# covox.net
KiCad netlist of a schematic drawn in EAGLE
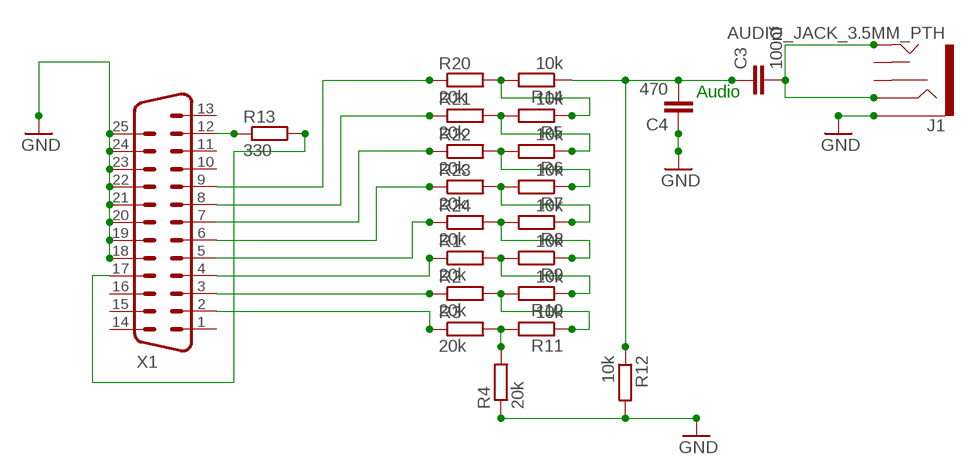
[diagram p0: schematic, sheet 1]

(export (version "E")
  (design (tool "Eeschema 10.0.6"))
  (components
    (comp (ref "C3")
      (value "100nf")
      (footprint "eagle-import:C0805K")
      (libsource (lib "eagle-import") (part "C-EUC0805K"))
    )
    (comp (ref "C4")
      (value "470")
      (footprint "eagle-import:C0805K")
      (libsource (lib "eagle-import") (part "C-EUC0805K"))
    )
    (comp (ref "J1")
      (value "AUDIO_JACK_3.5MM_PTH")
      (footprint "eagle-import:AUDIO-JACK")
      (libsource (lib "eagle-import") (part "AUDIO_JACK_3.5MM_PTH"))
    )
    (comp (ref "R1")
      (value "20k")
      (footprint "eagle-import:M0805")
      (libsource (lib "eagle-import") (part "R-EU_M0805"))
    )
    (comp (ref "R2")
      (value "20k")
      (footprint "eagle-import:M0805")
      (libsource (lib "eagle-import") (part "R-EU_M0805"))
    )
    (comp (ref "R3")
      (value "20k")
      (footprint "eagle-import:M0805")
      (libsource (lib "eagle-import") (part "R-EU_M0805"))
    )
    (comp (ref "R4")
      (value "20k")
      (footprint "eagle-import:M0805")
      (libsource (lib "eagle-import") (part "R-EU_M0805"))
    )
    (comp (ref "R5")
      (value "10k")
      (footprint "eagle-import:M0805")
      (libsource (lib "eagle-import") (part "R-EU_M0805"))
    )
    (comp (ref "R6")
      (value "10k")
      (footprint "eagle-import:M0805")
      (libsource (lib "eagle-import") (part "R-EU_M0805"))
    )
    (comp (ref "R7")
      (value "10k")
      (footprint "eagle-import:M0805")
      (libsource (lib "eagle-import") (part "R-EU_M0805"))
    )
    (comp (ref "R8")
      (value "10k")
      (footprint "eagle-import:M0805")
      (libsource (lib "eagle-import") (part "R-EU_M0805"))
    )
    (comp (ref "R9")
      (value "10k")
      (footprint "eagle-import:M0805")
      (libsource (lib "eagle-import") (part "R-EU_M0805"))
    )
    (comp (ref "R10")
      (value "10k")
      (footprint "eagle-import:M0805")
      (libsource (lib "eagle-import") (part "R-EU_M0805"))
    )
    (comp (ref "R11")
      (value "10k")
      (footprint "eagle-import:M0805")
      (libsource (lib "eagle-import") (part "R-EU_M0805"))
    )
    (comp (ref "R12")
      (value "10k")
      (footprint "eagle-import:M0805")
      (libsource (lib "eagle-import") (part "R-EU_M0805"))
    )
    (comp (ref "R13")
      (value "330")
      (footprint "eagle-import:M0805")
      (libsource (lib "eagle-import") (part "R-EU_M0805"))
    )
    (comp (ref "R14")
      (value "10k")
      (footprint "eagle-import:M0805")
      (libsource (lib "eagle-import") (part "R-EU_M0805"))
    )
    (comp (ref "R20")
      (value "20k")
      (footprint "eagle-import:M0805")
      (libsource (lib "eagle-import") (part "R-EU_M0805"))
    )
    (comp (ref "R21")
      (value "20k")
      (footprint "eagle-import:M0805")
      (libsource (lib "eagle-import") (part "R-EU_M0805"))
    )
    (comp (ref "R22")
      (value "20k")
      (footprint "eagle-import:M0805")
      (libsource (lib "eagle-import") (part "R-EU_M0805"))
    )
    (comp (ref "R23")
      (value "20k")
      (footprint "eagle-import:M0805")
      (libsource (lib "eagle-import") (part "R-EU_M0805"))
    )
    (comp (ref "R24")
      (value "20k")
      (footprint "eagle-import:M0805")
      (libsource (lib "eagle-import") (part "R-EU_M0805"))
    )
    (comp (ref "X1")
      (value "M25HP")
      (footprint "eagle-import:M25HP")
      (libsource (lib "eagle-import") (part "M25HP"))
    )
  )
  (nets
    (net (code "1") (name "GND") (class "Default")
      (node (ref "C4") (pin "1") (pinfunction "1_1") (pintype "passive"))
      (node (ref "J1") (pin "SLEEVE") (pinfunction "SLEEVE_SLEEVE") (pintype "bidirectional"))
      (node (ref "R12") (pin "2") (pinfunction "2_2") (pintype "passive"))
      (node (ref "R4") (pin "1") (pinfunction "1_1") (pintype "passive"))
      (node (ref "X1") (pin "18") (pinfunction "18_18") (pintype "passive"))
      (node (ref "X1") (pin "19") (pinfunction "19_19") (pintype "passive"))
      (node (ref "X1") (pin "20") (pinfunction "20_20") (pintype "passive"))
      (node (ref "X1") (pin "21") (pinfunction "21_21") (pintype "passive"))
      (node (ref "X1") (pin "22") (pinfunction "22_22") (pintype "passive"))
      (node (ref "X1") (pin "23") (pinfunction "23_23") (pintype "passive"))
      (node (ref "X1") (pin "24") (pinfunction "24_24") (pintype "passive"))
      (node (ref "X1") (pin "25") (pinfunction "25_25") (pintype "passive"))
    )
    (net (code "2") (name "Net-(C3-Pad1)") (class "Default")
      (node (ref "C3") (pin "1") (pinfunction "1_1") (pintype "passive"))
      (node (ref "C4") (pin "2") (pinfunction "2_2") (pintype "passive"))
      (node (ref "R12") (pin "1") (pinfunction "1_1") (pintype "passive"))
      (node (ref "R14") (pin "1") (pinfunction "1_1") (pintype "passive"))
    )
    (net (code "3") (name "Net-(C3-Pad2)") (class "Default")
      (node (ref "C3") (pin "2") (pinfunction "2_2") (pintype "passive"))
      (node (ref "J1") (pin "RING") (pinfunction "RING_RING") (pintype "bidirectional"))
      (node (ref "J1") (pin "TIP") (pinfunction "TIP_TIP") (pintype "bidirectional"))
    )
    (net (code "4") (name "Net-(R1-Pad1)") (class "Default")
      (node (ref "R1") (pin "1") (pinfunction "1_1") (pintype "passive"))
      (node (ref "X1") (pin "4") (pinfunction "4_4") (pintype "passive"))
    )
    (net (code "5") (name "Net-(R1-Pad2)") (class "Default")
      (node (ref "R1") (pin "2") (pinfunction "2_2") (pintype "passive"))
      (node (ref "R10") (pin "1") (pinfunction "1_1") (pintype "passive"))
      (node (ref "R9") (pin "2") (pinfunction "2_2") (pintype "passive"))
    )
    (net (code "6") (name "Net-(R2-Pad1)") (class "Default")
      (node (ref "R2") (pin "1") (pinfunction "1_1") (pintype "passive"))
      (node (ref "X1") (pin "3") (pinfunction "3_3") (pintype "passive"))
    )
    (net (code "7") (name "Net-(R3-Pad1)") (class "Default")
      (node (ref "R3") (pin "1") (pinfunction "1_1") (pintype "passive"))
      (node (ref "X1") (pin "2") (pinfunction "2_2") (pintype "passive"))
    )
    (net (code "8") (name "Net-(R10-Pad2)") (class "Default")
      (node (ref "R10") (pin "2") (pinfunction "2_2") (pintype "passive"))
      (node (ref "R11") (pin "1") (pinfunction "1_1") (pintype "passive"))
      (node (ref "R2") (pin "2") (pinfunction "2_2") (pintype "passive"))
    )
    (net (code "9") (name "Net-(R11-Pad2)") (class "Default")
      (node (ref "R11") (pin "2") (pinfunction "2_2") (pintype "passive"))
      (node (ref "R3") (pin "2") (pinfunction "2_2") (pintype "passive"))
      (node (ref "R4") (pin "2") (pinfunction "2_2") (pintype "passive"))
    )
    (net (code "10") (name "Net-(R13-Pad1)") (class "Default")
      (node (ref "R13") (pin "1") (pinfunction "1_1") (pintype "passive"))
      (node (ref "X1") (pin "12") (pinfunction "12_12") (pintype "passive"))
    )
    (net (code "11") (name "Net-(R13-Pad2)") (class "Default")
      (node (ref "R13") (pin "2") (pinfunction "2_2") (pintype "passive"))
      (node (ref "X1") (pin "17") (pinfunction "17_17") (pintype "passive"))
    )
    (net (code "12") (name "Net-(R14-Pad2)") (class "Default")
      (node (ref "R14") (pin "2") (pinfunction "2_2") (pintype "passive"))
      (node (ref "R20") (pin "2") (pinfunction "2_2") (pintype "passive"))
      (node (ref "R5") (pin "1") (pinfunction "1_1") (pintype "passive"))
    )
    (net (code "13") (name "Net-(R20-Pad1)") (class "Default")
      (node (ref "R20") (pin "1") (pinfunction "1_1") (pintype "passive"))
      (node (ref "X1") (pin "9") (pinfunction "9_9") (pintype "passive"))
    )
    (net (code "14") (name "Net-(R21-Pad1)") (class "Default")
      (node (ref "R21") (pin "1") (pinfunction "1_1") (pintype "passive"))
      (node (ref "X1") (pin "8") (pinfunction "8_8") (pintype "passive"))
    )
    (net (code "15") (name "Net-(R21-Pad2)") (class "Default")
      (node (ref "R21") (pin "2") (pinfunction "2_2") (pintype "passive"))
      (node (ref "R5") (pin "2") (pinfunction "2_2") (pintype "passive"))
      (node (ref "R6") (pin "1") (pinfunction "1_1") (pintype "passive"))
    )
    (net (code "16") (name "Net-(R22-Pad1)") (class "Default")
      (node (ref "R22") (pin "1") (pinfunction "1_1") (pintype "passive"))
      (node (ref "X1") (pin "7") (pinfunction "7_7") (pintype "passive"))
    )
    (net (code "17") (name "Net-(R22-Pad2)") (class "Default")
      (node (ref "R22") (pin "2") (pinfunction "2_2") (pintype "passive"))
      (node (ref "R6") (pin "2") (pinfunction "2_2") (pintype "passive"))
      (node (ref "R7") (pin "1") (pinfunction "1_1") (pintype "passive"))
    )
    (net (code "18") (name "Net-(R23-Pad1)") (class "Default")
      (node (ref "R23") (pin "1") (pinfunction "1_1") (pintype "passive"))
      (node (ref "X1") (pin "6") (pinfunction "6_6") (pintype "passive"))
    )
    (net (code "19") (name "Net-(R23-Pad2)") (class "Default")
      (node (ref "R23") (pin "2") (pinfunction "2_2") (pintype "passive"))
      (node (ref "R7") (pin "2") (pinfunction "2_2") (pintype "passive"))
      (node (ref "R8") (pin "1") (pinfunction "1_1") (pintype "passive"))
    )
    (net (code "20") (name "Net-(R24-Pad1)") (class "Default")
      (node (ref "R24") (pin "1") (pinfunction "1_1") (pintype "passive"))
      (node (ref "X1") (pin "5") (pinfunction "5_5") (pintype "passive"))
    )
    (net (code "21") (name "Net-(R24-Pad2)") (class "Default")
      (node (ref "R24") (pin "2") (pinfunction "2_2") (pintype "passive"))
      (node (ref "R8") (pin "2") (pinfunction "2_2") (pintype "passive"))
      (node (ref "R9") (pin "1") (pinfunction "1_1") (pintype "passive"))
    )
    (net (code "22") (name "unconnected-(J1-PadRSH)") (class "Default")
      (node (ref "J1") (pin "RSH") (pinfunction "RSH_RSH") (pintype "bidirectional"))
    )
    (net (code "23") (name "unconnected-(J1-PadTSH)") (class "Default")
      (node (ref "J1") (pin "TSH") (pinfunction "TSH_TSH") (pintype "bidirectional"))
    )
    (net (code "24") (name "unconnected-(X1-Pad1)") (class "Default")
      (node (ref "X1") (pin "1") (pinfunction "1_1") (pintype "passive"))
    )
    (net (code "25") (name "unconnected-(X1-Pad10)") (class "Default")
      (node (ref "X1") (pin "10") (pinfunction "10_10") (pintype "passive"))
    )
    (net (code "26") (name "unconnected-(X1-Pad11)") (class "Default")
      (node (ref "X1") (pin "11") (pinfunction "11_11") (pintype "passive"))
    )
    (net (code "27") (name "unconnected-(X1-Pad13)") (class "Default")
      (node (ref "X1") (pin "13") (pinfunction "13_13") (pintype "passive"))
    )
    (net (code "28") (name "unconnected-(X1-Pad14)") (class "Default")
      (node (ref "X1") (pin "14") (pinfunction "14_14") (pintype "passive"))
    )
    (net (code "29") (name "unconnected-(X1-Pad15)") (class "Default")
      (node (ref "X1") (pin "15") (pinfunction "15_15") (pintype "passive"))
    )
    (net (code "30") (name "unconnected-(X1-Pad16)") (class "Default")
      (node (ref "X1") (pin "16") (pinfunction "16_16") (pintype "passive"))
    )
  )
)
